# pi-zigbee-poe-rtc.net
KiCad netlist of a schematic drawn in EAGLE
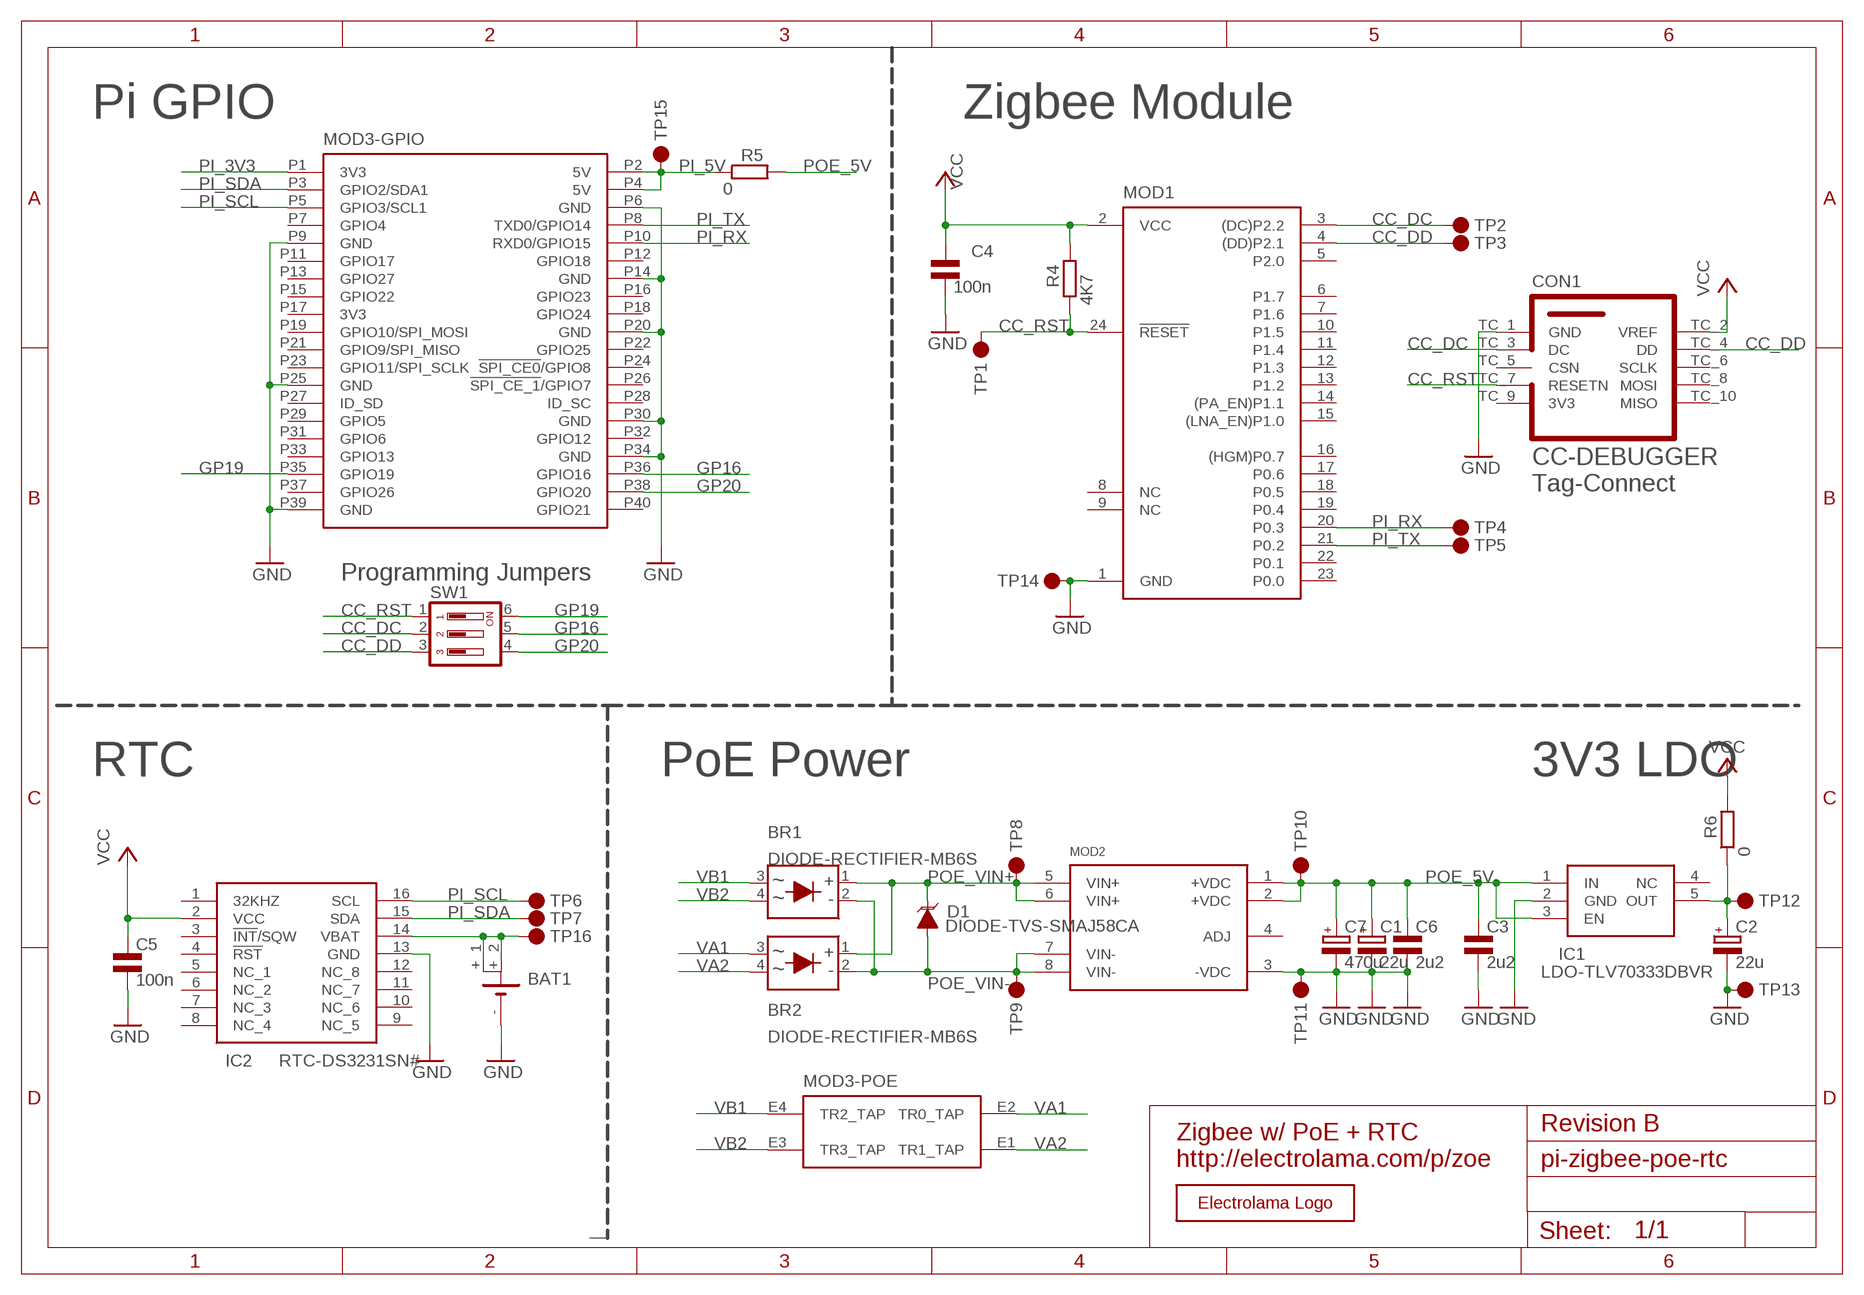
[diagram p0: schematic, sheet 1]

(export (version "E")
  (design (tool "Eeschema 10.0.6"))
  (components
    (comp (ref "BAT1")
      (value "BATTERY")
      (footprint "eagle-import:KEYSTONE_3001")
      (libsource (lib "eagle-import") (part "BATTERY"))
    )
    (comp (ref "BR1")
      (value "DIODE-RECTIFIER-MB6S")
      (footprint "eagle-import:SOP254P665X270-4N")
      (fields
        (field (name "MANUFACTURER_PART_NUMBER") "MB6S-TP")
        (field (name "MOUSER_PART_NUMBER") "833-MB6S-TP")
      )
      (libsource (lib "eagle-import") (part "DIODE-RECTIFIER-MB6S"))
    )
    (comp (ref "BR2")
      (value "DIODE-RECTIFIER-MB6S")
      (footprint "eagle-import:SOP254P665X270-4N")
      (fields
        (field (name "MANUFACTURER_PART_NUMBER") "MB6S-TP")
        (field (name "MOUSER_PART_NUMBER") "833-MB6S-TP")
      )
      (libsource (lib "eagle-import") (part "DIODE-RECTIFIER-MB6S"))
    )
    (comp (ref "C1")
      (value "22u")
      (footprint "eagle-import:_CAP_TANT_A_3216-18R")
      (libsource (lib "eagle-import") (part "CAP-POL-TANT-A"))
    )
    (comp (ref "C2")
      (value "22u")
      (footprint "eagle-import:_CAP_TANT_A_3216-18R")
      (libsource (lib "eagle-import") (part "CAP-POL-TANT-A"))
    )
    (comp (ref "C3")
      (value "2u2")
      (footprint "eagle-import:_PKG_C_0603")
      (libsource (lib "eagle-import") (part "CAP-0603"))
    )
    (comp (ref "C4")
      (value "100n")
      (footprint "eagle-import:_PKG_C_0603")
      (libsource (lib "eagle-import") (part "CAP-0603"))
    )
    (comp (ref "C5")
      (value "100n")
      (footprint "eagle-import:_PKG_C_0603")
      (libsource (lib "eagle-import") (part "CAP-0603"))
    )
    (comp (ref "C6")
      (value "2u2")
      (footprint "eagle-import:_PKG_C_0603")
      (libsource (lib "eagle-import") (part "CAP-0603"))
    )
    (comp (ref "C7")
      (value "470u")
      (footprint "eagle-import:_CAP_ELCO_D8_L10.5")
      (libsource (lib "eagle-import") (part "CAP-POL-ELCO-D8-L10.5"))
    )
    (comp (ref "CON1")
      (value "TC2050-IDC-NL_CC-DEBUGGER")
      (footprint "eagle-import:TC2050-IDC-NL")
      (libsource (lib "eagle-import") (part "TC2050-IDC-NL_CC-DEBUGGER"))
    )
    (comp (ref "D1")
      (value "DIODE-TVS-SMAJ58CA")
      (footprint "eagle-import:DIOM5126X250N-NOPOL")
      (fields (field (name "MANUFACTURER_PART_NUMBER") "SMAJ58CA"))
      (libsource (lib "eagle-import") (part "DIODE-TVS-SMAJ58CA"))
    )
    (comp (ref "IC1")
      (value "LDO-TLV70333DBVR")
      (footprint "eagle-import:SOT95P280X145-5N")
      (fields
        (field (name "MANUFACTURER_PART_NUMBER") "TLV70333DBVR")
        (field (name "MOUSER_PART_NUMBER") "595-TLV70333DBVR")
      )
      (libsource (lib "eagle-import") (part "LDO-TLV70333DBVR"))
    )
    (comp (ref "IC2")
      (value "RTC-DS3231SN#")
      (footprint "eagle-import:SOIC127P1032X265-16N")
      (fields
        (field (name "MANUFACTURER_PART_NUMBER") "DS3231SN#")
        (field (name "MOUSER_PART_NUMBER") "700-DS3231SN#")
        (field (name "RS_PART_NUMBER") "1897251")
      )
      (libsource (lib "eagle-import") (part "RTC-DS3231SN#"))
    )
    (comp (ref "MOD1")
      (value "EBYTE-E18-MS1PA1")
      (footprint "eagle-import:EBYTE-E18-MS1PA1")
      (libsource (lib "eagle-import") (part "EBYTE-E18-MS1PA1"))
    )
    (comp (ref "MOD2")
      (value "SILVERTEL_AG9800M")
      (footprint "eagle-import:SILVERTEL_AG9800M")
      (libsource (lib "eagle-import") (part "SILVERTEL_AG9800M"))
    )
    (comp (ref "MOD3")
      (value "RPI-HAT-FULL")
      (footprint "eagle-import:RPI-HAT-FULL")
      (libsource (lib "eagle-import") (part "RPI-HAT-FULL"))
    )
    (comp (ref "R4")
      (value "4K7")
      (footprint "eagle-import:_PKG_C_0603")
      (libsource (lib "eagle-import") (part "RES-0603"))
    )
    (comp (ref "R5")
      (value "0")
      (footprint "eagle-import:TP_DUAL_1206")
      (libsource (lib "eagle-import") (part "TP_DUAL_1206"))
    )
    (comp (ref "R6")
      (value "0")
      (footprint "eagle-import:TP_DUAL_1206")
      (libsource (lib "eagle-import") (part "TP_DUAL_1206"))
    )
    (comp (ref "SW1")
      (value "SWITCH-DIP03-SMD")
      (footprint "eagle-import:DSHP03TS-S")
      (libsource (lib "eagle-import") (part "SWITCH-DIP03-SMD"))
    )
    (comp (ref "TP1") (value "TP") (footprint "eagle-import:TP") (libsource (lib "eagle-import") (part "TP")))
    (comp (ref "TP2") (value "TP") (footprint "eagle-import:TP") (libsource (lib "eagle-import") (part "TP")))
    (comp (ref "TP3") (value "TP") (footprint "eagle-import:TP") (libsource (lib "eagle-import") (part "TP")))
    (comp (ref "TP4") (value "TP") (footprint "eagle-import:TP") (libsource (lib "eagle-import") (part "TP")))
    (comp (ref "TP5") (value "TP") (footprint "eagle-import:TP") (libsource (lib "eagle-import") (part "TP")))
    (comp (ref "TP6") (value "TP") (footprint "eagle-import:TP") (libsource (lib "eagle-import") (part "TP")))
    (comp (ref "TP7") (value "TP") (footprint "eagle-import:TP") (libsource (lib "eagle-import") (part "TP")))
    (comp (ref "TP8") (value "TP") (footprint "eagle-import:TP") (libsource (lib "eagle-import") (part "TP")))
    (comp (ref "TP9") (value "TP") (footprint "eagle-import:TP") (libsource (lib "eagle-import") (part "TP")))
    (comp (ref "TP10")
      (value "TP")
      (footprint "eagle-import:TP")
      (libsource (lib "eagle-import") (part "TP"))
    )
    (comp (ref "TP11")
      (value "TP")
      (footprint "eagle-import:TP")
      (libsource (lib "eagle-import") (part "TP"))
    )
    (comp (ref "TP12")
      (value "TP")
      (footprint "eagle-import:TP")
      (libsource (lib "eagle-import") (part "TP"))
    )
    (comp (ref "TP13")
      (value "TP")
      (footprint "eagle-import:TP")
      (libsource (lib "eagle-import") (part "TP"))
    )
    (comp (ref "TP14")
      (value "TP")
      (footprint "eagle-import:TP")
      (libsource (lib "eagle-import") (part "TP"))
    )
    (comp (ref "TP15")
      (value "TP")
      (footprint "eagle-import:TP")
      (libsource (lib "eagle-import") (part "TP"))
    )
    (comp (ref "TP16")
      (value "TP")
      (footprint "eagle-import:TP")
      (libsource (lib "eagle-import") (part "TP"))
    )
    (comp (ref "U$1")
      (value "LOGO-ELECTROLAMA")
      (footprint "eagle-import:ELECTROLAMA")
      (libsource (lib "eagle-import") (part "LOGO-ELECTROLAMA"))
    )
  )
  (nets
    (net (code "1") (name "/CC_DC") (class "Default")
      (node (ref "CON1") (pin "TC_3") (pinfunction "DC_TC_3") (pintype "bidirectional"))
      (node (ref "MOD1") (pin "3") (pinfunction "(DC)P2.2_3") (pintype "bidirectional"))
      (node (ref "SW1") (pin "2") (pinfunction "2_2") (pintype "passive"))
      (node (ref "TP2") (pin "TP") (pinfunction "TP_TP") (pintype "bidirectional"))
    )
    (net (code "2") (name "/CC_DD") (class "Default")
      (node (ref "CON1") (pin "TC_4") (pinfunction "DD_TC_4") (pintype "bidirectional"))
      (node (ref "MOD1") (pin "4") (pinfunction "(DD)P2.1_4") (pintype "bidirectional"))
      (node (ref "SW1") (pin "3") (pinfunction "3_3") (pintype "passive"))
      (node (ref "TP3") (pin "TP") (pinfunction "TP_TP") (pintype "bidirectional"))
    )
    (net (code "3") (name "/CC_RST") (class "Default")
      (node (ref "CON1") (pin "TC_7") (pinfunction "RESETN_TC_7") (pintype "bidirectional"))
      (node (ref "MOD1") (pin "24") (pinfunction "~{RESET}_24") (pintype "input"))
      (node (ref "R4") (pin "1") (pinfunction "1_1") (pintype "passive"))
      (node (ref "SW1") (pin "1") (pinfunction "1_1") (pintype "passive"))
      (node (ref "TP1") (pin "TP") (pinfunction "TP_TP") (pintype "bidirectional"))
    )
    (net (code "4") (name "/GP16") (class "Default")
      (node (ref "MOD3") (pin "P36") (pinfunction "GPIO16_P36") (pintype "bidirectional"))
      (node (ref "SW1") (pin "5") (pinfunction "5_5") (pintype "passive"))
    )
    (net (code "5") (name "/GP19") (class "Default")
      (node (ref "MOD3") (pin "P35") (pinfunction "GPIO19_P35") (pintype "bidirectional"))
      (node (ref "SW1") (pin "6") (pinfunction "6_6") (pintype "passive"))
    )
    (net (code "6") (name "/GP20") (class "Default")
      (node (ref "MOD3") (pin "P38") (pinfunction "GPIO20_P38") (pintype "bidirectional"))
      (node (ref "SW1") (pin "4") (pinfunction "4_4") (pintype "passive"))
    )
    (net (code "7") (name "/PI_3V3") (class "Default")
      (node (ref "MOD3") (pin "P1") (pinfunction "3V3_P1") (pintype "bidirectional"))
    )
    (net (code "8") (name "/PI_5V") (class "Default")
      (node (ref "MOD3") (pin "P2") (pinfunction "5V_P2") (pintype "bidirectional"))
      (node (ref "MOD3") (pin "P4") (pinfunction "5V_P4") (pintype "bidirectional"))
      (node (ref "R5") (pin "1") (pinfunction "1_1") (pintype "passive"))
      (node (ref "TP15") (pin "TP") (pinfunction "TP_TP") (pintype "bidirectional"))
    )
    (net (code "9") (name "/PI_RX") (class "Default")
      (node (ref "MOD1") (pin "20") (pinfunction "P0.3_20") (pintype "bidirectional"))
      (node (ref "MOD3") (pin "P10") (pinfunction "RXD0/GPIO15_P10") (pintype "bidirectional"))
      (node (ref "TP4") (pin "TP") (pinfunction "TP_TP") (pintype "bidirectional"))
    )
    (net (code "10") (name "/PI_SCL") (class "Default")
      (node (ref "IC2") (pin "16") (pinfunction "SCL_16") (pintype "bidirectional"))
      (node (ref "MOD3") (pin "P5") (pinfunction "GPIO3/SCL1_P5") (pintype "bidirectional"))
      (node (ref "TP6") (pin "TP") (pinfunction "TP_TP") (pintype "bidirectional"))
    )
    (net (code "11") (name "/PI_SDA") (class "Default")
      (node (ref "IC2") (pin "15") (pinfunction "SDA_15") (pintype "bidirectional"))
      (node (ref "MOD3") (pin "P3") (pinfunction "GPIO2/SDA1_P3") (pintype "bidirectional"))
      (node (ref "TP7") (pin "TP") (pinfunction "TP_TP") (pintype "bidirectional"))
    )
    (net (code "12") (name "/PI_TX") (class "Default")
      (node (ref "MOD1") (pin "21") (pinfunction "P0.2_21") (pintype "bidirectional"))
      (node (ref "MOD3") (pin "P8") (pinfunction "TXD0/GPIO14_P8") (pintype "bidirectional"))
      (node (ref "TP5") (pin "TP") (pinfunction "TP_TP") (pintype "bidirectional"))
    )
    (net (code "13") (name "/POE_5V") (class "Default")
      (node (ref "C1") (pin "+") (pinfunction "+_+") (pintype "passive"))
      (node (ref "C3") (pin "1") (pinfunction "1_1") (pintype "passive"))
      (node (ref "C6") (pin "1") (pinfunction "1_1") (pintype "passive"))
      (node (ref "C7") (pin "+") (pinfunction "+_+") (pintype "passive"))
      (node (ref "IC1") (pin "1") (pinfunction "IN_1") (pintype "bidirectional"))
      (node (ref "IC1") (pin "3") (pinfunction "EN_3") (pintype "bidirectional"))
      (node (ref "MOD2") (pin "1") (pinfunction "+VDC_1") (pintype "bidirectional"))
      (node (ref "MOD2") (pin "2") (pinfunction "+VDC_2") (pintype "bidirectional"))
      (node (ref "R5") (pin "2") (pinfunction "2_2") (pintype "passive"))
      (node (ref "TP10") (pin "TP") (pinfunction "TP_TP") (pintype "bidirectional"))
    )
    (net (code "14") (name "/POE_VIN+") (class "Default")
      (node (ref "BR1") (pin "1") (pinfunction "+_1") (pintype "bidirectional"))
      (node (ref "BR2") (pin "1") (pinfunction "+_1") (pintype "bidirectional"))
      (node (ref "D1") (pin "1") (pinfunction "C_1") (pintype "passive"))
      (node (ref "MOD2") (pin "5") (pinfunction "VIN+_5") (pintype "bidirectional"))
      (node (ref "MOD2") (pin "6") (pinfunction "VIN+_6") (pintype "bidirectional"))
      (node (ref "TP8") (pin "TP") (pinfunction "TP_TP") (pintype "bidirectional"))
    )
    (net (code "15") (name "/POE_VIN-") (class "Default")
      (node (ref "BR1") (pin "2") (pinfunction "-_2") (pintype "bidirectional"))
      (node (ref "BR2") (pin "2") (pinfunction "-_2") (pintype "bidirectional"))
      (node (ref "D1") (pin "2") (pinfunction "A_2") (pintype "passive"))
      (node (ref "MOD2") (pin "7") (pinfunction "VIN-_7") (pintype "bidirectional"))
      (node (ref "MOD2") (pin "8") (pinfunction "VIN-_8") (pintype "bidirectional"))
      (node (ref "TP9") (pin "TP") (pinfunction "TP_TP") (pintype "bidirectional"))
    )
    (net (code "16") (name "/VA1") (class "Default")
      (node (ref "BR2") (pin "3") (pinfunction "~_3") (pintype "bidirectional"))
      (node (ref "MOD3") (pin "E2") (pinfunction "TR0_TAP_E2") (pintype "bidirectional"))
    )
    (net (code "17") (name "/VA2") (class "Default")
      (node (ref "BR2") (pin "4") (pinfunction "~_4") (pintype "bidirectional"))
      (node (ref "MOD3") (pin "E1") (pinfunction "TR1_TAP_E1") (pintype "bidirectional"))
    )
    (net (code "18") (name "/VB1") (class "Default")
      (node (ref "BR1") (pin "3") (pinfunction "~_3") (pintype "bidirectional"))
      (node (ref "MOD3") (pin "E4") (pinfunction "TR2_TAP_E4") (pintype "bidirectional"))
    )
    (net (code "19") (name "/VB2") (class "Default")
      (node (ref "BR1") (pin "4") (pinfunction "~_4") (pintype "bidirectional"))
      (node (ref "MOD3") (pin "E3") (pinfunction "TR3_TAP_E3") (pintype "bidirectional"))
    )
    (net (code "20") (name "GND") (class "Default")
      (node (ref "BAT1") (pin "-") (pinfunction "-_-") (pintype "passive"))
      (node (ref "C1") (pin "-") (pinfunction "-_-") (pintype "passive"))
      (node (ref "C2") (pin "-") (pinfunction "-_-") (pintype "passive"))
      (node (ref "C3") (pin "2") (pinfunction "2_2") (pintype "passive"))
      (node (ref "C4") (pin "2") (pinfunction "2_2") (pintype "passive"))
      (node (ref "C5") (pin "2") (pinfunction "2_2") (pintype "passive"))
      (node (ref "C6") (pin "2") (pinfunction "2_2") (pintype "passive"))
      (node (ref "C7") (pin "-") (pinfunction "-_-") (pintype "passive"))
      (node (ref "CON1") (pin "TC_1") (pinfunction "GND_TC_1") (pintype "bidirectional"))
      (node (ref "IC1") (pin "2") (pinfunction "GND_2") (pintype "bidirectional"))
      (node (ref "IC2") (pin "13") (pinfunction "GND_13") (pintype "power_in"))
      (node (ref "MOD1") (pin "1") (pinfunction "GND_1") (pintype "power_in"))
      (node (ref "MOD2") (pin "3") (pinfunction "-VDC_3") (pintype "bidirectional"))
      (node (ref "MOD3") (pin "P14") (pinfunction "GND_P14") (pintype "bidirectional"))
      (node (ref "MOD3") (pin "P20") (pinfunction "GND_P20") (pintype "bidirectional"))
      (node (ref "MOD3") (pin "P25") (pinfunction "GND_P25") (pintype "bidirectional"))
      (node (ref "MOD3") (pin "P30") (pinfunction "GND_P30") (pintype "bidirectional"))
      (node (ref "MOD3") (pin "P34") (pinfunction "GND_P34") (pintype "bidirectional"))
      (node (ref "MOD3") (pin "P39") (pinfunction "GND_P39") (pintype "bidirectional"))
      (node (ref "MOD3") (pin "P6") (pinfunction "GND_P6") (pintype "bidirectional"))
      (node (ref "MOD3") (pin "P9") (pinfunction "GND_P9") (pintype "bidirectional"))
      (node (ref "TP11") (pin "TP") (pinfunction "TP_TP") (pintype "bidirectional"))
      (node (ref "TP13") (pin "TP") (pinfunction "TP_TP") (pintype "bidirectional"))
      (node (ref "TP14") (pin "TP") (pinfunction "TP_TP") (pintype "bidirectional"))
    )
    (net (code "21") (name "Net-(BAT1-+1)") (class "Default")
      (node (ref "BAT1") (pin "+_1") (pinfunction "+1_+_1") (pintype "passive"))
      (node (ref "BAT1") (pin "+_2") (pinfunction "+2_+_2") (pintype "passive"))
      (node (ref "IC2") (pin "14") (pinfunction "VBAT_14") (pintype "bidirectional"))
      (node (ref "TP16") (pin "TP") (pinfunction "TP_TP") (pintype "bidirectional"))
    )
    (net (code "22") (name "Net-(IC1-OUT)") (class "Default")
      (node (ref "C2") (pin "+") (pinfunction "+_+") (pintype "passive"))
      (node (ref "IC1") (pin "5") (pinfunction "OUT_5") (pintype "bidirectional"))
      (node (ref "R6") (pin "1") (pinfunction "1_1") (pintype "passive"))
      (node (ref "TP12") (pin "TP") (pinfunction "TP_TP") (pintype "bidirectional"))
    )
    (net (code "23") (name "VCC") (class "Default")
      (node (ref "C4") (pin "1") (pinfunction "1_1") (pintype "passive"))
      (node (ref "C5") (pin "1") (pinfunction "1_1") (pintype "passive"))
      (node (ref "CON1") (pin "TC_2") (pinfunction "VREF_TC_2") (pintype "bidirectional"))
      (node (ref "IC2") (pin "2") (pinfunction "VCC_2") (pintype "power_in"))
      (node (ref "MOD1") (pin "2") (pinfunction "VCC_2") (pintype "power_in"))
      (node (ref "R4") (pin "2") (pinfunction "2_2") (pintype "passive"))
      (node (ref "R6") (pin "2") (pinfunction "2_2") (pintype "passive"))
    )
    (net (code "24") (name "unconnected-(CON1-3V3-PadTC_9)") (class "Default")
      (node (ref "CON1") (pin "TC_9") (pinfunction "3V3_TC_9") (pintype "bidirectional"))
    )
    (net (code "25") (name "unconnected-(CON1-CSN-PadTC_5)") (class "Default")
      (node (ref "CON1") (pin "TC_5") (pinfunction "CSN_TC_5") (pintype "bidirectional"))
    )
    (net (code "26") (name "unconnected-(CON1-MISO-PadTC_10)") (class "Default")
      (node (ref "CON1") (pin "TC_10") (pinfunction "MISO_TC_10") (pintype "bidirectional"))
    )
    (net (code "27") (name "unconnected-(CON1-MOSI-PadTC_8)") (class "Default")
      (node (ref "CON1") (pin "TC_8") (pinfunction "MOSI_TC_8") (pintype "bidirectional"))
    )
    (net (code "28") (name "unconnected-(CON1-SCLK-PadTC_6)") (class "Default")
      (node (ref "CON1") (pin "TC_6") (pinfunction "SCLK_TC_6") (pintype "bidirectional"))
    )
    (net (code "29") (name "unconnected-(IC1-NC-Pad4)") (class "Default")
      (node (ref "IC1") (pin "4") (pinfunction "NC_4") (pintype "no_connect"))
    )
    (net (code "30") (name "unconnected-(IC2-32KHZ-Pad1)") (class "Default")
      (node (ref "IC2") (pin "1") (pinfunction "32KHZ_1") (pintype "bidirectional"))
    )
    (net (code "31") (name "unconnected-(IC2-NC_1-Pad5)") (class "Default")
      (node (ref "IC2") (pin "5") (pinfunction "NC_1_5") (pintype "bidirectional"))
    )
    (net (code "32") (name "unconnected-(IC2-NC_2-Pad6)") (class "Default")
      (node (ref "IC2") (pin "6") (pinfunction "NC_2_6") (pintype "bidirectional"))
    )
    (net (code "33") (name "unconnected-(IC2-NC_3-Pad7)") (class "Default")
      (node (ref "IC2") (pin "7") (pinfunction "NC_3_7") (pintype "bidirectional"))
    )
    (net (code "34") (name "unconnected-(IC2-NC_4-Pad8)") (class "Default")
      (node (ref "IC2") (pin "8") (pinfunction "NC_4_8") (pintype "bidirectional"))
    )
    (net (code "35") (name "unconnected-(IC2-NC_5-Pad9)") (class "Default")
      (node (ref "IC2") (pin "9") (pinfunction "NC_5_9") (pintype "bidirectional"))
    )
    (net (code "36") (name "unconnected-(IC2-NC_6-Pad10)") (class "Default")
      (node (ref "IC2") (pin "10") (pinfunction "NC_6_10") (pintype "bidirectional"))
    )
    (net (code "37") (name "unconnected-(IC2-NC_7-Pad11)") (class "Default")
      (node (ref "IC2") (pin "11") (pinfunction "NC_7_11") (pintype "bidirectional"))
    )
    (net (code "38") (name "unconnected-(IC2-NC_8-Pad12)") (class "Default")
      (node (ref "IC2") (pin "12") (pinfunction "NC_8_12") (pintype "bidirectional"))
    )
    (net (code "39") (name "unconnected-(IC2-~{INT}{slash}SQW-Pad3)") (class "Default")
      (node (ref "IC2") (pin "3") (pinfunction "~{INT}/SQW_3") (pintype "input"))
    )
    (net (code "40") (name "unconnected-(IC2-~{RST}-Pad4)") (class "Default")
      (node (ref "IC2") (pin "4") (pinfunction "~{RST}_4") (pintype "input"))
    )
    (net (code "41") (name "unconnected-(MOD1-(HGM)P0.7-Pad16)") (class "Default")
      (node (ref "MOD1") (pin "16") (pinfunction "(HGM)P0.7_16") (pintype "output"))
    )
    (net (code "42") (name "unconnected-(MOD1-(LNA_EN)P1.0-Pad15)") (class "Default")
      (node (ref "MOD1") (pin "15") (pinfunction "(LNA_EN)P1.0_15") (pintype "output"))
    )
    (net (code "43") (name "unconnected-(MOD1-(PA_EN)P1.1-Pad14)") (class "Default")
      (node (ref "MOD1") (pin "14") (pinfunction "(PA_EN)P1.1_14") (pintype "output"))
    )
    (net (code "44") (name "unconnected-(MOD1-NC-Pad8)") (class "Default")
      (node (ref "MOD1") (pin "8") (pinfunction "NC_8") (pintype "no_connect"))
    )
    (net (code "45") (name "unconnected-(MOD1-NC-Pad9)") (class "Default")
      (node (ref "MOD1") (pin "9") (pinfunction "NC_9") (pintype "no_connect"))
    )
    (net (code "46") (name "unconnected-(MOD1-P0.0-Pad23)") (class "Default")
      (node (ref "MOD1") (pin "23") (pinfunction "P0.0_23") (pintype "bidirectional"))
    )
    (net (code "47") (name "unconnected-(MOD1-P0.1-Pad22)") (class "Default")
      (node (ref "MOD1") (pin "22") (pinfunction "P0.1_22") (pintype "bidirectional"))
    )
    (net (code "48") (name "unconnected-(MOD1-P0.4-Pad19)") (class "Default")
      (node (ref "MOD1") (pin "19") (pinfunction "P0.4_19") (pintype "bidirectional"))
    )
    (net (code "49") (name "unconnected-(MOD1-P0.5-Pad18)") (class "Default")
      (node (ref "MOD1") (pin "18") (pinfunction "P0.5_18") (pintype "bidirectional"))
    )
    (net (code "50") (name "unconnected-(MOD1-P0.6-Pad17)") (class "Default")
      (node (ref "MOD1") (pin "17") (pinfunction "P0.6_17") (pintype "bidirectional"))
    )
    (net (code "51") (name "unconnected-(MOD1-P1.2-Pad13)") (class "Default")
      (node (ref "MOD1") (pin "13") (pinfunction "P1.2_13") (pintype "bidirectional"))
    )
    (net (code "52") (name "unconnected-(MOD1-P1.3-Pad12)") (class "Default")
      (node (ref "MOD1") (pin "12") (pinfunction "P1.3_12") (pintype "bidirectional"))
    )
    (net (code "53") (name "unconnected-(MOD1-P1.4-Pad11)") (class "Default")
      (node (ref "MOD1") (pin "11") (pinfunction "P1.4_11") (pintype "bidirectional"))
    )
    (net (code "54") (name "unconnected-(MOD1-P1.5-Pad10)") (class "Default")
      (node (ref "MOD1") (pin "10") (pinfunction "P1.5_10") (pintype "bidirectional"))
    )
    (net (code "55") (name "unconnected-(MOD1-P1.6-Pad7)") (class "Default")
      (node (ref "MOD1") (pin "7") (pinfunction "P1.6_7") (pintype "bidirectional"))
    )
    (net (code "56") (name "unconnected-(MOD1-P1.7-Pad6)") (class "Default")
      (node (ref "MOD1") (pin "6") (pinfunction "P1.7_6") (pintype "bidirectional"))
    )
    (net (code "57") (name "unconnected-(MOD1-P2.0-Pad5)") (class "Default")
      (node (ref "MOD1") (pin "5") (pinfunction "P2.0_5") (pintype "bidirectional"))
    )
    (net (code "58") (name "unconnected-(MOD2-ADJ-Pad4)") (class "Default")
      (node (ref "MOD2") (pin "4") (pinfunction "ADJ_4") (pintype "bidirectional"))
    )
    (net (code "59") (name "unconnected-(MOD3A-3V3-PadP17)") (class "Default")
      (node (ref "MOD3") (pin "P17") (pinfunction "3V3_P17") (pintype "bidirectional"))
    )
    (net (code "60") (name "unconnected-(MOD3A-GPIO4-PadP7)") (class "Default")
      (node (ref "MOD3") (pin "P7") (pinfunction "GPIO4_P7") (pintype "bidirectional"))
    )
    (net (code "61") (name "unconnected-(MOD3A-GPIO5-PadP29)") (class "Default")
      (node (ref "MOD3") (pin "P29") (pinfunction "GPIO5_P29") (pintype "bidirectional"))
    )
    (net (code "62") (name "unconnected-(MOD3A-GPIO6-PadP31)") (class "Default")
      (node (ref "MOD3") (pin "P31") (pinfunction "GPIO6_P31") (pintype "bidirectional"))
    )
    (net (code "63") (name "unconnected-(MOD3A-GPIO9{slash}SPI_MISO-PadP21)") (class "Default")
      (node (ref "MOD3") (pin "P21") (pinfunction "GPIO9/SPI_MISO_P21") (pintype "bidirectional"))
    )
    (net (code "64") (name "unconnected-(MOD3A-GPIO10{slash}SPI_MOSI-PadP19)") (class "Default")
      (node (ref "MOD3") (pin "P19") (pinfunction "GPIO10/SPI_MOSI_P19") (pintype "bidirectional"))
    )
    (net (code "65") (name "unconnected-(MOD3A-GPIO11{slash}SPI_SCLK-PadP23)") (class "Default")
      (node (ref "MOD3") (pin "P23") (pinfunction "GPIO11/SPI_SCLK_P23") (pintype "bidirectional"))
    )
    (net (code "66") (name "unconnected-(MOD3A-GPIO12-PadP32)") (class "Default")
      (node (ref "MOD3") (pin "P32") (pinfunction "GPIO12_P32") (pintype "bidirectional"))
    )
    (net (code "67") (name "unconnected-(MOD3A-GPIO13-PadP33)") (class "Default")
      (node (ref "MOD3") (pin "P33") (pinfunction "GPIO13_P33") (pintype "bidirectional"))
    )
    (net (code "68") (name "unconnected-(MOD3A-GPIO17-PadP11)") (class "Default")
      (node (ref "MOD3") (pin "P11") (pinfunction "GPIO17_P11") (pintype "bidirectional"))
    )
    (net (code "69") (name "unconnected-(MOD3A-GPIO18-PadP12)") (class "Default")
      (node (ref "MOD3") (pin "P12") (pinfunction "GPIO18_P12") (pintype "bidirectional"))
    )
    (net (code "70") (name "unconnected-(MOD3A-GPIO21-PadP40)") (class "Default")
      (node (ref "MOD3") (pin "P40") (pinfunction "GPIO21_P40") (pintype "bidirectional"))
    )
    (net (code "71") (name "unconnected-(MOD3A-GPIO22-PadP15)") (class "Default")
      (node (ref "MOD3") (pin "P15") (pinfunction "GPIO22_P15") (pintype "bidirectional"))
    )
    (net (code "72") (name "unconnected-(MOD3A-GPIO23-PadP16)") (class "Default")
      (node (ref "MOD3") (pin "P16") (pinfunction "GPIO23_P16") (pintype "bidirectional"))
    )
    (net (code "73") (name "unconnected-(MOD3A-GPIO24-PadP18)") (class "Default")
      (node (ref "MOD3") (pin "P18") (pinfunction "GPIO24_P18") (pintype "bidirectional"))
    )
    (net (code "74") (name "unconnected-(MOD3A-GPIO25-PadP22)") (class "Default")
      (node (ref "MOD3") (pin "P22") (pinfunction "GPIO25_P22") (pintype "bidirectional"))
    )
    (net (code "75") (name "unconnected-(MOD3A-GPIO26-PadP37)") (class "Default")
      (node (ref "MOD3") (pin "P37") (pinfunction "GPIO26_P37") (pintype "bidirectional"))
    )
    (net (code "76") (name "unconnected-(MOD3A-GPIO27-PadP13)") (class "Default")
      (node (ref "MOD3") (pin "P13") (pinfunction "GPIO27_P13") (pintype "bidirectional"))
    )
    (net (code "77") (name "unconnected-(MOD3A-ID_SC-PadP28)") (class "Default")
      (node (ref "MOD3") (pin "P28") (pinfunction "ID_SC_P28") (pintype "bidirectional"))
    )
    (net (code "78") (name "unconnected-(MOD3A-ID_SD-PadP27)") (class "Default")
      (node (ref "MOD3") (pin "P27") (pinfunction "ID_SD_P27") (pintype "bidirectional"))
    )
    (net (code "79") (name "unconnected-(MOD3A-~{SPI_CE0}{slash}GPIO8-PadP24)") (class "Default")
      (node (ref "MOD3") (pin "P24") (pinfunction "~{SPI_CE0}/GPIO8_P24") (pintype "bidirectional"))
    )
    (net (code "80") (name "unconnected-(MOD3A-~{SPI_CE_1}{slash}GPIO7-PadP26)") (class "Default")
      (node (ref "MOD3") (pin "P26") (pinfunction "~{SPI_CE_1}/GPIO7_P26") (pintype "bidirectional"))
    )
  )
)
